# mymote-esp8266.net
KiCad netlist of a schematic drawn in EAGLE
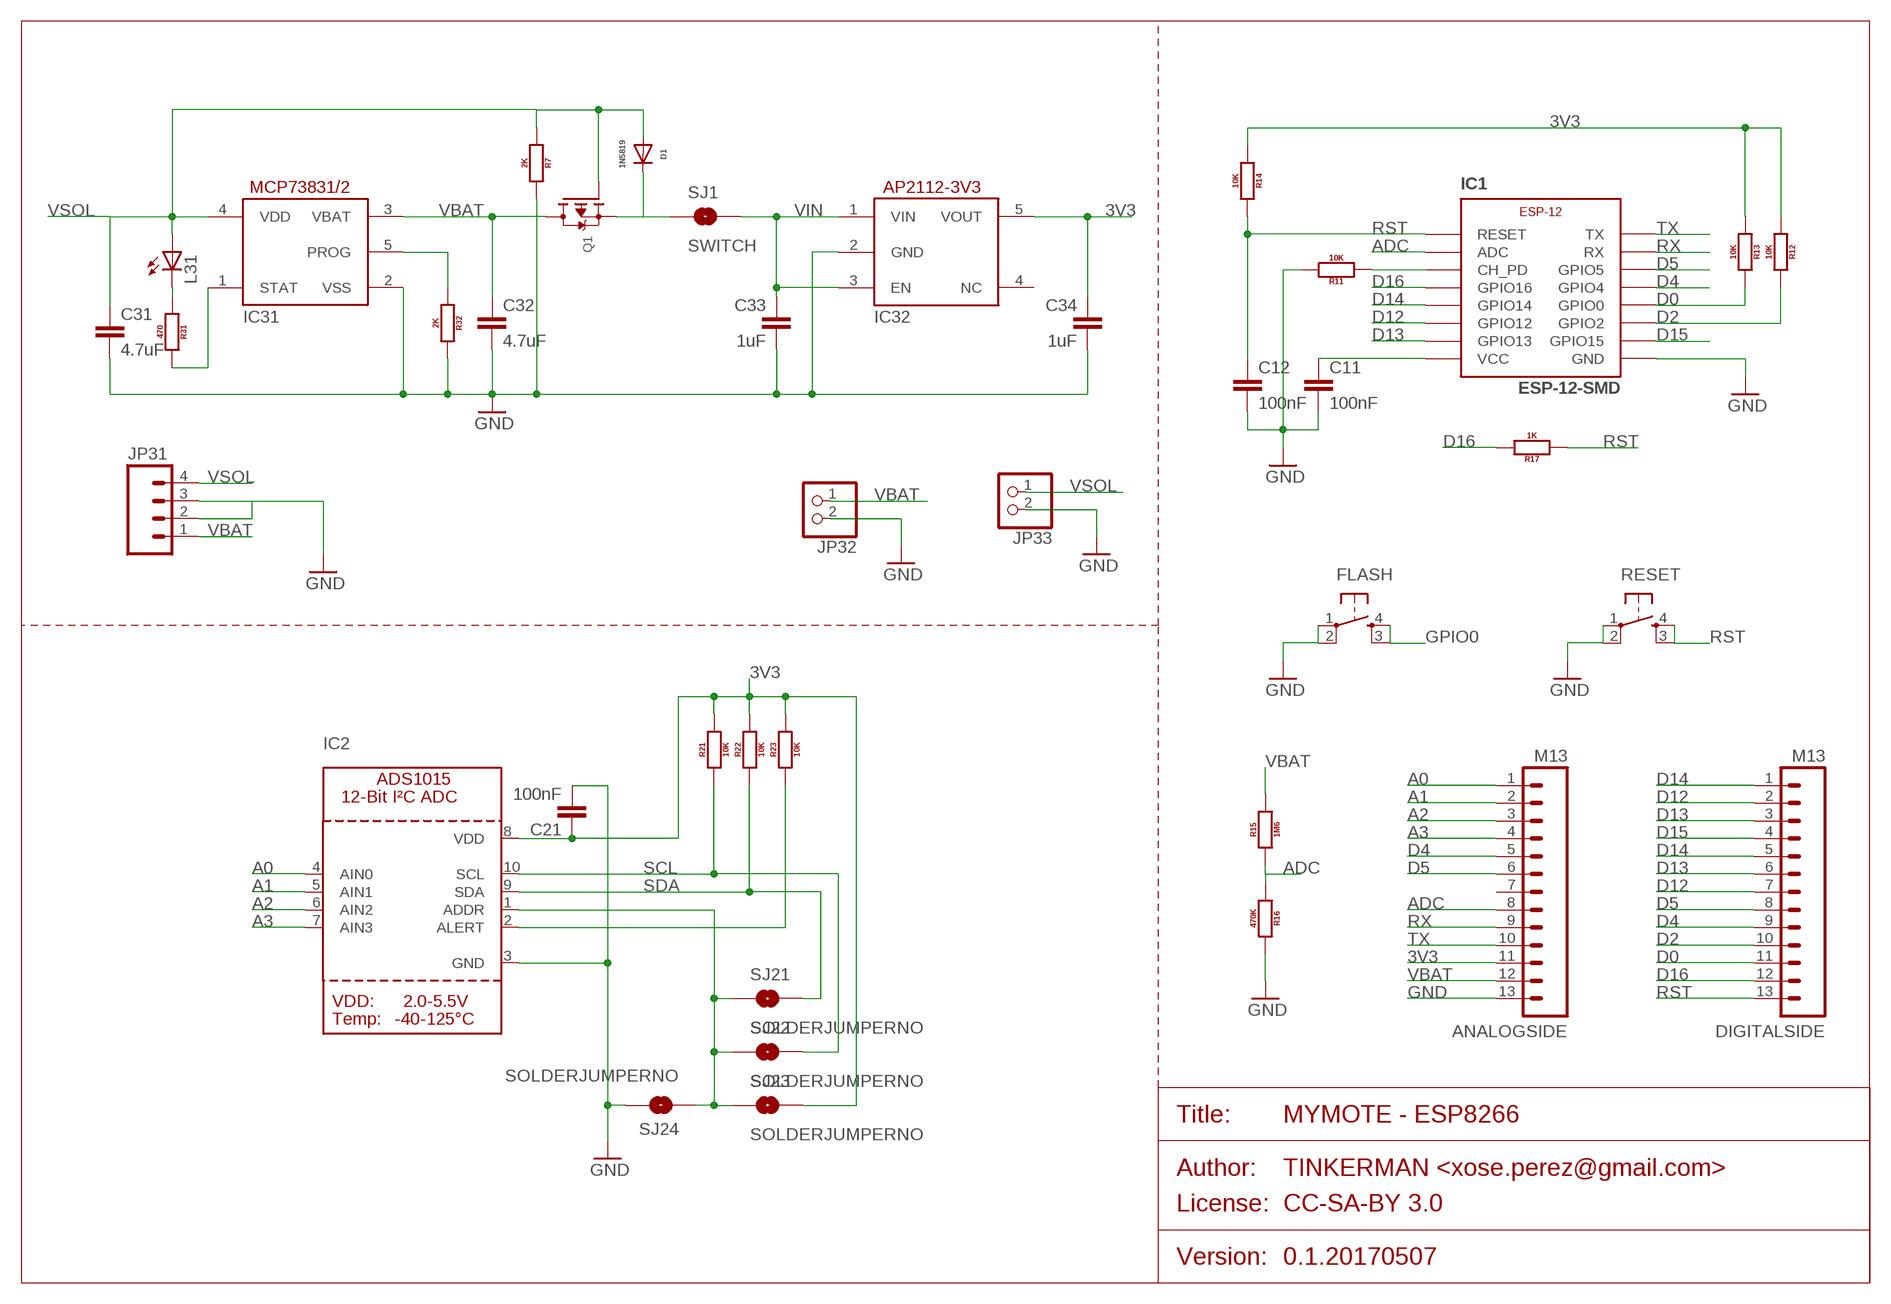
[diagram p0: schematic, sheet 1]

(export (version "E")
  (design (tool "Eeschema 10.0.6"))
  (components
    (comp (ref "ANALOGSIDE")
      (value "M13")
      (footprint "eagle-import:1X13_NO_SILK")
      (libsource (lib "eagle-import") (part "M13"))
    )
    (comp (ref "C11")
      (value "100nF")
      (footprint "eagle-import:0805")
      (libsource (lib "eagle-import") (part "C-EU0805"))
    )
    (comp (ref "C12")
      (value "100nF")
      (footprint "eagle-import:0805")
      (libsource (lib "eagle-import") (part "C-EU0805"))
    )
    (comp (ref "C21")
      (value "100nF")
      (footprint "eagle-import:0805")
      (libsource (lib "eagle-import") (part "C-EU0805"))
    )
    (comp (ref "C31")
      (value "4.7uF")
      (footprint "eagle-import:0805")
      (libsource (lib "eagle-import") (part "C-EU0805"))
    )
    (comp (ref "C32")
      (value "4.7uF")
      (footprint "eagle-import:0805")
      (libsource (lib "eagle-import") (part "C-EU0805"))
    )
    (comp (ref "C33")
      (value "1uF")
      (footprint "eagle-import:0805")
      (libsource (lib "eagle-import") (part "C-EU0805"))
    )
    (comp (ref "C34")
      (value "1uF")
      (footprint "eagle-import:0805")
      (libsource (lib "eagle-import") (part "C-EU0805"))
    )
    (comp (ref "D1")
      (value "1N5819")
      (footprint "eagle-import:0805_DIODE")
      (libsource (lib "eagle-import") (part "DIODE-SMD"))
    )
    (comp (ref "DIGITALSIDE")
      (value "M13")
      (footprint "eagle-import:1X13_NO_SILK")
      (libsource (lib "eagle-import") (part "M13"))
    )
    (comp (ref "FLASH")
      (value "TACTILE_BUTTON_SMD")
      (footprint "eagle-import:TACTILE-BUTTON-SMD")
      (libsource (lib "eagle-import") (part "TACTILE_BUTTON_SMD"))
    )
    (comp (ref "IC1")
      (value "ESP-12-SMD")
      (footprint "eagle-import:ESP-12-SMD")
      (libsource (lib "eagle-import") (part "ESP-12-SMD"))
    )
    (comp (ref "IC2")
      (value "ADC_ADS1015")
      (footprint "eagle-import:MSOP10")
      (libsource (lib "eagle-import") (part "ADC_ADS1015"))
    )
    (comp (ref "IC31")
      (value "MCP73831/OT")
      (footprint "eagle-import:SOT23-5L")
      (libsource (lib "eagle-import") (part "MCP73831/OT"))
    )
    (comp (ref "IC32")
      (value "AP2112-3V3")
      (footprint "eagle-import:SOT23-5L")
      (libsource (lib "eagle-import") (part "AP2112-3V3"))
    )
    (comp (ref "JP31")
      (value "M04PTH")
      (footprint "eagle-import:1X04")
      (libsource (lib "eagle-import") (part "M04PTH"))
    )
    (comp (ref "JP32")
      (value "JST_2PIN-SMT-RA")
      (footprint "eagle-import:JST-PH-2-SMT-RA")
      (libsource (lib "eagle-import") (part "JST_2PIN-SMT-RA"))
    )
    (comp (ref "JP33")
      (value "JST_2PIN-SMT-RA")
      (footprint "eagle-import:JST-PH-2-SMT-RA")
      (libsource (lib "eagle-import") (part "JST_2PIN-SMT-RA"))
    )
    (comp (ref "L31")
      (value "LED_0805")
      (footprint "eagle-import:0805_DIODE")
      (libsource (lib "eagle-import") (part "LED_0805"))
    )
    (comp (ref "Q1")
      (value "MOSFET-PWIDE")
      (footprint "eagle-import:SOT23-WIDE")
      (libsource (lib "eagle-import") (part "MOSFET-PWIDE"))
    )
    (comp (ref "R7")
      (value "2K")
      (footprint "eagle-import:0805")
      (libsource (lib "eagle-import") (part "RESISTOR0805"))
    )
    (comp (ref "R11")
      (value "10K")
      (footprint "eagle-import:0805")
      (libsource (lib "eagle-import") (part "RESISTOR0805"))
    )
    (comp (ref "R12")
      (value "10K")
      (footprint "eagle-import:0805")
      (libsource (lib "eagle-import") (part "RESISTOR0805"))
    )
    (comp (ref "R13")
      (value "10K")
      (footprint "eagle-import:0805")
      (libsource (lib "eagle-import") (part "RESISTOR0805"))
    )
    (comp (ref "R14")
      (value "10K")
      (footprint "eagle-import:0805")
      (libsource (lib "eagle-import") (part "RESISTOR0805"))
    )
    (comp (ref "R15")
      (value "1M6")
      (footprint "eagle-import:0805")
      (libsource (lib "eagle-import") (part "RESISTOR0805"))
    )
    (comp (ref "R16")
      (value "470K")
      (footprint "eagle-import:0805")
      (libsource (lib "eagle-import") (part "RESISTOR0805"))
    )
    (comp (ref "R17")
      (value "1K")
      (footprint "eagle-import:0805")
      (libsource (lib "eagle-import") (part "RESISTOR0805"))
    )
    (comp (ref "R21")
      (value "10K")
      (footprint "eagle-import:0805")
      (libsource (lib "eagle-import") (part "RESISTOR0805"))
    )
    (comp (ref "R22")
      (value "10K")
      (footprint "eagle-import:0805")
      (libsource (lib "eagle-import") (part "RESISTOR0805"))
    )
    (comp (ref "R23")
      (value "10K")
      (footprint "eagle-import:0805")
      (libsource (lib "eagle-import") (part "RESISTOR0805"))
    )
    (comp (ref "R31")
      (value "470")
      (footprint "eagle-import:0805")
      (libsource (lib "eagle-import") (part "RESISTOR0805"))
    )
    (comp (ref "R32")
      (value "2K")
      (footprint "eagle-import:0805")
      (libsource (lib "eagle-import") (part "RESISTOR0805"))
    )
    (comp (ref "RESET")
      (value "TACTILE_BUTTON_SMD")
      (footprint "eagle-import:TACTILE-BUTTON-SMD")
      (libsource (lib "eagle-import") (part "TACTILE_BUTTON_SMD"))
    )
    (comp (ref "SJ1")
      (value "SWITCH")
      (footprint "eagle-import:SJ_2S-TRACE-PTH")
      (libsource (lib "eagle-import") (part "SOLDERJUMPERTRACE-PTH"))
    )
    (comp (ref "SJ21")
      (value "SOLDERJUMPERNO")
      (footprint "eagle-import:SJ_2S-NO")
      (libsource (lib "eagle-import") (part "SOLDERJUMPERNO"))
    )
    (comp (ref "SJ22")
      (value "SOLDERJUMPERNO")
      (footprint "eagle-import:SJ_2S-NO")
      (libsource (lib "eagle-import") (part "SOLDERJUMPERNO"))
    )
    (comp (ref "SJ23")
      (value "SOLDERJUMPERNO")
      (footprint "eagle-import:SJ_2S-NO")
      (libsource (lib "eagle-import") (part "SOLDERJUMPERNO"))
    )
    (comp (ref "SJ24")
      (value "SOLDERJUMPERNO")
      (footprint "eagle-import:SJ_2S-NO")
      (libsource (lib "eagle-import") (part "SOLDERJUMPERNO"))
    )
  )
  (nets
    (net (code "1") (name "/3V3") (class "Default")
      (node (ref "ANALOGSIDE") (pin "11") (pinfunction "11_11") (pintype "passive"))
      (node (ref "C11") (pin "1") (pinfunction "1_1") (pintype "passive"))
      (node (ref "C21") (pin "1") (pinfunction "1_1") (pintype "passive"))
      (node (ref "C34") (pin "1") (pinfunction "1_1") (pintype "passive"))
      (node (ref "IC1") (pin "VCC") (pinfunction "VCC_VCC") (pintype "bidirectional"))
      (node (ref "IC2") (pin "8") (pinfunction "VDD_8") (pintype "bidirectional"))
      (node (ref "IC32") (pin "5") (pinfunction "VOUT_5") (pintype "power_in"))
      (node (ref "R12") (pin "1") (pinfunction "1_1") (pintype "passive"))
      (node (ref "R13") (pin "1") (pinfunction "1_1") (pintype "passive"))
      (node (ref "R14") (pin "1") (pinfunction "1_1") (pintype "passive"))
      (node (ref "R21") (pin "2") (pinfunction "2_2") (pintype "passive"))
      (node (ref "R22") (pin "2") (pinfunction "2_2") (pintype "passive"))
      (node (ref "R23") (pin "2") (pinfunction "2_2") (pintype "passive"))
      (node (ref "SJ23") (pin "2") (pinfunction "2_2") (pintype "passive"))
    )
    (net (code "2") (name "/A0") (class "Default")
      (node (ref "ANALOGSIDE") (pin "1") (pinfunction "1_1") (pintype "passive"))
      (node (ref "IC2") (pin "4") (pinfunction "AIN0_4") (pintype "bidirectional"))
    )
    (net (code "3") (name "/A1") (class "Default")
      (node (ref "ANALOGSIDE") (pin "2") (pinfunction "2_2") (pintype "passive"))
      (node (ref "IC2") (pin "5") (pinfunction "AIN1_5") (pintype "bidirectional"))
    )
    (net (code "4") (name "/A2") (class "Default")
      (node (ref "ANALOGSIDE") (pin "3") (pinfunction "3_3") (pintype "passive"))
      (node (ref "IC2") (pin "6") (pinfunction "AIN2_6") (pintype "bidirectional"))
    )
    (net (code "5") (name "/A3") (class "Default")
      (node (ref "ANALOGSIDE") (pin "4") (pinfunction "4_4") (pintype "passive"))
      (node (ref "IC2") (pin "7") (pinfunction "AIN3_7") (pintype "bidirectional"))
    )
    (net (code "6") (name "/ADC") (class "Default")
      (node (ref "ANALOGSIDE") (pin "8") (pinfunction "8_8") (pintype "passive"))
      (node (ref "IC1") (pin "ADC") (pinfunction "ADC_ADC") (pintype "bidirectional"))
      (node (ref "R15") (pin "1") (pinfunction "1_1") (pintype "passive"))
      (node (ref "R16") (pin "1") (pinfunction "1_1") (pintype "passive"))
    )
    (net (code "7") (name "/D0") (class "Default")
      (node (ref "DIGITALSIDE") (pin "11") (pinfunction "11_11") (pintype "passive"))
      (node (ref "IC1") (pin "GPIO0") (pinfunction "GPIO0_GPIO0") (pintype "bidirectional"))
      (node (ref "R13") (pin "2") (pinfunction "2_2") (pintype "passive"))
    )
    (net (code "8") (name "/D2") (class "Default")
      (node (ref "DIGITALSIDE") (pin "10") (pinfunction "10_10") (pintype "passive"))
      (node (ref "IC1") (pin "GPIO2") (pinfunction "GPIO2_GPIO2") (pintype "bidirectional"))
      (node (ref "R12") (pin "2") (pinfunction "2_2") (pintype "passive"))
    )
    (net (code "9") (name "/D4") (class "Default")
      (node (ref "ANALOGSIDE") (pin "5") (pinfunction "5_5") (pintype "passive"))
      (node (ref "DIGITALSIDE") (pin "9") (pinfunction "9_9") (pintype "passive"))
      (node (ref "IC1") (pin "GPIO4") (pinfunction "GPIO4_GPIO4") (pintype "bidirectional"))
    )
    (net (code "10") (name "/D5") (class "Default")
      (node (ref "ANALOGSIDE") (pin "6") (pinfunction "6_6") (pintype "passive"))
      (node (ref "DIGITALSIDE") (pin "8") (pinfunction "8_8") (pintype "passive"))
      (node (ref "IC1") (pin "GPIO5") (pinfunction "GPIO5_GPIO5") (pintype "bidirectional"))
    )
    (net (code "11") (name "/D12") (class "Default")
      (node (ref "DIGITALSIDE") (pin "2") (pinfunction "2_2") (pintype "passive"))
      (node (ref "DIGITALSIDE") (pin "7") (pinfunction "7_7") (pintype "passive"))
      (node (ref "IC1") (pin "GPIO12") (pinfunction "GPIO12_GPIO12") (pintype "bidirectional"))
    )
    (net (code "12") (name "/D13") (class "Default")
      (node (ref "DIGITALSIDE") (pin "3") (pinfunction "3_3") (pintype "passive"))
      (node (ref "DIGITALSIDE") (pin "6") (pinfunction "6_6") (pintype "passive"))
      (node (ref "IC1") (pin "GPIO13") (pinfunction "GPIO13_GPIO13") (pintype "bidirectional"))
    )
    (net (code "13") (name "/D14") (class "Default")
      (node (ref "DIGITALSIDE") (pin "1") (pinfunction "1_1") (pintype "passive"))
      (node (ref "DIGITALSIDE") (pin "5") (pinfunction "5_5") (pintype "passive"))
      (node (ref "IC1") (pin "GPIO14") (pinfunction "GPIO14_GPIO14") (pintype "bidirectional"))
    )
    (net (code "14") (name "/D15") (class "Default")
      (node (ref "DIGITALSIDE") (pin "4") (pinfunction "4_4") (pintype "passive"))
      (node (ref "IC1") (pin "GPIO15") (pinfunction "GPIO15_GPIO15") (pintype "bidirectional"))
    )
    (net (code "15") (name "/D16") (class "Default")
      (node (ref "DIGITALSIDE") (pin "12") (pinfunction "12_12") (pintype "passive"))
      (node (ref "IC1") (pin "GPIO16") (pinfunction "GPIO16_GPIO16") (pintype "bidirectional"))
      (node (ref "R17") (pin "2") (pinfunction "2_2") (pintype "passive"))
    )
    (net (code "16") (name "/GPIO0") (class "Default")
      (node (ref "FLASH") (pin "3") (pinfunction "SWB2_3") (pintype "passive"))
      (node (ref "FLASH") (pin "4") (pinfunction "SWA2_4") (pintype "passive"))
    )
    (net (code "17") (name "/RST") (class "Default")
      (node (ref "C12") (pin "1") (pinfunction "1_1") (pintype "passive"))
      (node (ref "DIGITALSIDE") (pin "13") (pinfunction "13_13") (pintype "passive"))
      (node (ref "IC1") (pin "RESET") (pinfunction "RESET_RESET") (pintype "bidirectional"))
      (node (ref "R14") (pin "2") (pinfunction "2_2") (pintype "passive"))
      (node (ref "R17") (pin "1") (pinfunction "1_1") (pintype "passive"))
      (node (ref "RESET") (pin "3") (pinfunction "SWB2_3") (pintype "passive"))
      (node (ref "RESET") (pin "4") (pinfunction "SWA2_4") (pintype "passive"))
    )
    (net (code "18") (name "/RX") (class "Default")
      (node (ref "ANALOGSIDE") (pin "9") (pinfunction "9_9") (pintype "passive"))
      (node (ref "IC1") (pin "RX") (pinfunction "RX_RX") (pintype "bidirectional"))
    )
    (net (code "19") (name "/SCL") (class "Default")
      (node (ref "IC2") (pin "10") (pinfunction "SCL_10") (pintype "bidirectional"))
      (node (ref "R21") (pin "1") (pinfunction "1_1") (pintype "passive"))
      (node (ref "SJ22") (pin "2") (pinfunction "2_2") (pintype "passive"))
    )
    (net (code "20") (name "/SDA") (class "Default")
      (node (ref "IC2") (pin "9") (pinfunction "SDA_9") (pintype "bidirectional"))
      (node (ref "R22") (pin "1") (pinfunction "1_1") (pintype "passive"))
      (node (ref "SJ21") (pin "2") (pinfunction "2_2") (pintype "passive"))
    )
    (net (code "21") (name "/TX") (class "Default")
      (node (ref "ANALOGSIDE") (pin "10") (pinfunction "10_10") (pintype "passive"))
      (node (ref "IC1") (pin "TX") (pinfunction "TX_TX") (pintype "bidirectional"))
    )
    (net (code "22") (name "/VBAT") (class "Default")
      (node (ref "ANALOGSIDE") (pin "12") (pinfunction "12_12") (pintype "passive"))
      (node (ref "C32") (pin "1") (pinfunction "1_1") (pintype "passive"))
      (node (ref "IC31") (pin "3") (pinfunction "VBAT_3") (pintype "bidirectional"))
      (node (ref "JP31") (pin "1") (pinfunction "1_1") (pintype "passive"))
      (node (ref "JP32") (pin "1") (pinfunction "2_1") (pintype "passive"))
      (node (ref "Q1") (pin "3") (pinfunction "D_3") (pintype "passive"))
      (node (ref "R15") (pin "2") (pinfunction "2_2") (pintype "passive"))
    )
    (net (code "23") (name "/VIN") (class "Default")
      (node (ref "C33") (pin "1") (pinfunction "1_1") (pintype "passive"))
      (node (ref "IC32") (pin "1") (pinfunction "VIN_1") (pintype "power_in"))
      (node (ref "IC32") (pin "3") (pinfunction "EN_3") (pintype "input"))
      (node (ref "SJ1") (pin "2") (pinfunction "2_2") (pintype "passive"))
    )
    (net (code "24") (name "/VSOL") (class "Default")
      (node (ref "C31") (pin "1") (pinfunction "1_1") (pintype "passive"))
      (node (ref "D1") (pin "A") (pinfunction "A_A") (pintype "passive"))
      (node (ref "IC31") (pin "4") (pinfunction "VDD_4") (pintype "power_in"))
      (node (ref "JP31") (pin "4") (pinfunction "4_4") (pintype "passive"))
      (node (ref "JP33") (pin "1") (pinfunction "2_1") (pintype "passive"))
      (node (ref "L31") (pin "A") (pinfunction "A_A") (pintype "passive"))
      (node (ref "Q1") (pin "1") (pinfunction "G_1") (pintype "passive"))
      (node (ref "R7") (pin "1") (pinfunction "1_1") (pintype "passive"))
    )
    (net (code "25") (name "GND") (class "Default")
      (node (ref "ANALOGSIDE") (pin "13") (pinfunction "13_13") (pintype "passive"))
      (node (ref "C11") (pin "2") (pinfunction "2_2") (pintype "passive"))
      (node (ref "C12") (pin "2") (pinfunction "2_2") (pintype "passive"))
      (node (ref "C21") (pin "2") (pinfunction "2_2") (pintype "passive"))
      (node (ref "C31") (pin "2") (pinfunction "2_2") (pintype "passive"))
      (node (ref "C32") (pin "2") (pinfunction "2_2") (pintype "passive"))
      (node (ref "C33") (pin "2") (pinfunction "2_2") (pintype "passive"))
      (node (ref "C34") (pin "2") (pinfunction "2_2") (pintype "passive"))
      (node (ref "FLASH") (pin "1") (pinfunction "SWA1_1") (pintype "passive"))
      (node (ref "FLASH") (pin "2") (pinfunction "SWB1_2") (pintype "passive"))
      (node (ref "IC1") (pin "GND") (pinfunction "GND_GND") (pintype "bidirectional"))
      (node (ref "IC2") (pin "3") (pinfunction "GND_3") (pintype "bidirectional"))
      (node (ref "IC31") (pin "2") (pinfunction "VSS_2") (pintype "power_in"))
      (node (ref "IC32") (pin "2") (pinfunction "GND_2") (pintype "power_in"))
      (node (ref "JP31") (pin "2") (pinfunction "2_2") (pintype "passive"))
      (node (ref "JP31") (pin "3") (pinfunction "3_3") (pintype "passive"))
      (node (ref "JP32") (pin "2") (pinfunction "1_2") (pintype "passive"))
      (node (ref "JP33") (pin "2") (pinfunction "1_2") (pintype "passive"))
      (node (ref "R11") (pin "2") (pinfunction "2_2") (pintype "passive"))
      (node (ref "R16") (pin "2") (pinfunction "2_2") (pintype "passive"))
      (node (ref "R32") (pin "2") (pinfunction "2_2") (pintype "passive"))
      (node (ref "R7") (pin "2") (pinfunction "2_2") (pintype "passive"))
      (node (ref "RESET") (pin "1") (pinfunction "SWA1_1") (pintype "passive"))
      (node (ref "RESET") (pin "2") (pinfunction "SWB1_2") (pintype "passive"))
      (node (ref "SJ24") (pin "2") (pinfunction "2_2") (pintype "passive"))
    )
    (net (code "26") (name "Net-(IC1-PadCH_PD)") (class "Default")
      (node (ref "IC1") (pin "CH_PD") (pinfunction "CH_PD_CH_PD") (pintype "bidirectional"))
      (node (ref "R11") (pin "1") (pinfunction "1_1") (pintype "passive"))
    )
    (net (code "27") (name "Net-(IC2-ADDR)") (class "Default")
      (node (ref "IC2") (pin "1") (pinfunction "ADDR_1") (pintype "bidirectional"))
      (node (ref "SJ21") (pin "1") (pinfunction "1_1") (pintype "passive"))
      (node (ref "SJ22") (pin "1") (pinfunction "1_1") (pintype "passive"))
      (node (ref "SJ23") (pin "1") (pinfunction "1_1") (pintype "passive"))
      (node (ref "SJ24") (pin "1") (pinfunction "1_1") (pintype "passive"))
    )
    (net (code "28") (name "Net-(IC2-ALERT)") (class "Default")
      (node (ref "IC2") (pin "2") (pinfunction "ALERT_2") (pintype "bidirectional"))
      (node (ref "R23") (pin "1") (pinfunction "1_1") (pintype "passive"))
    )
    (net (code "29") (name "Net-(IC31-PROG)") (class "Default")
      (node (ref "IC31") (pin "5") (pinfunction "PROG_5") (pintype "input"))
      (node (ref "R32") (pin "1") (pinfunction "1_1") (pintype "passive"))
    )
    (net (code "30") (name "Net-(IC31-STAT)") (class "Default")
      (node (ref "IC31") (pin "1") (pinfunction "STAT_1") (pintype "output"))
      (node (ref "R31") (pin "2") (pinfunction "2_2") (pintype "passive"))
    )
    (net (code "31") (name "Net-(L31-PadC)") (class "Default")
      (node (ref "L31") (pin "C") (pinfunction "C_C") (pintype "passive"))
      (node (ref "R31") (pin "1") (pinfunction "1_1") (pintype "passive"))
    )
    (net (code "32") (name "Net-(Q1-S)") (class "Default")
      (node (ref "D1") (pin "C") (pinfunction "C_C") (pintype "passive"))
      (node (ref "Q1") (pin "2") (pinfunction "S_2") (pintype "passive"))
      (node (ref "SJ1") (pin "1") (pinfunction "1_1") (pintype "passive"))
    )
    (net (code "33") (name "unconnected-(ANALOGSIDE-Pad7)") (class "Default")
      (node (ref "ANALOGSIDE") (pin "7") (pinfunction "7_7") (pintype "passive"))
    )
    (net (code "34") (name "unconnected-(IC32-NC-Pad4)") (class "Default")
      (node (ref "IC32") (pin "4") (pinfunction "NC_4") (pintype "no_connect"))
    )
  )
)
